# wmk.net
KiCad netlist of a schematic drawn in EAGLE
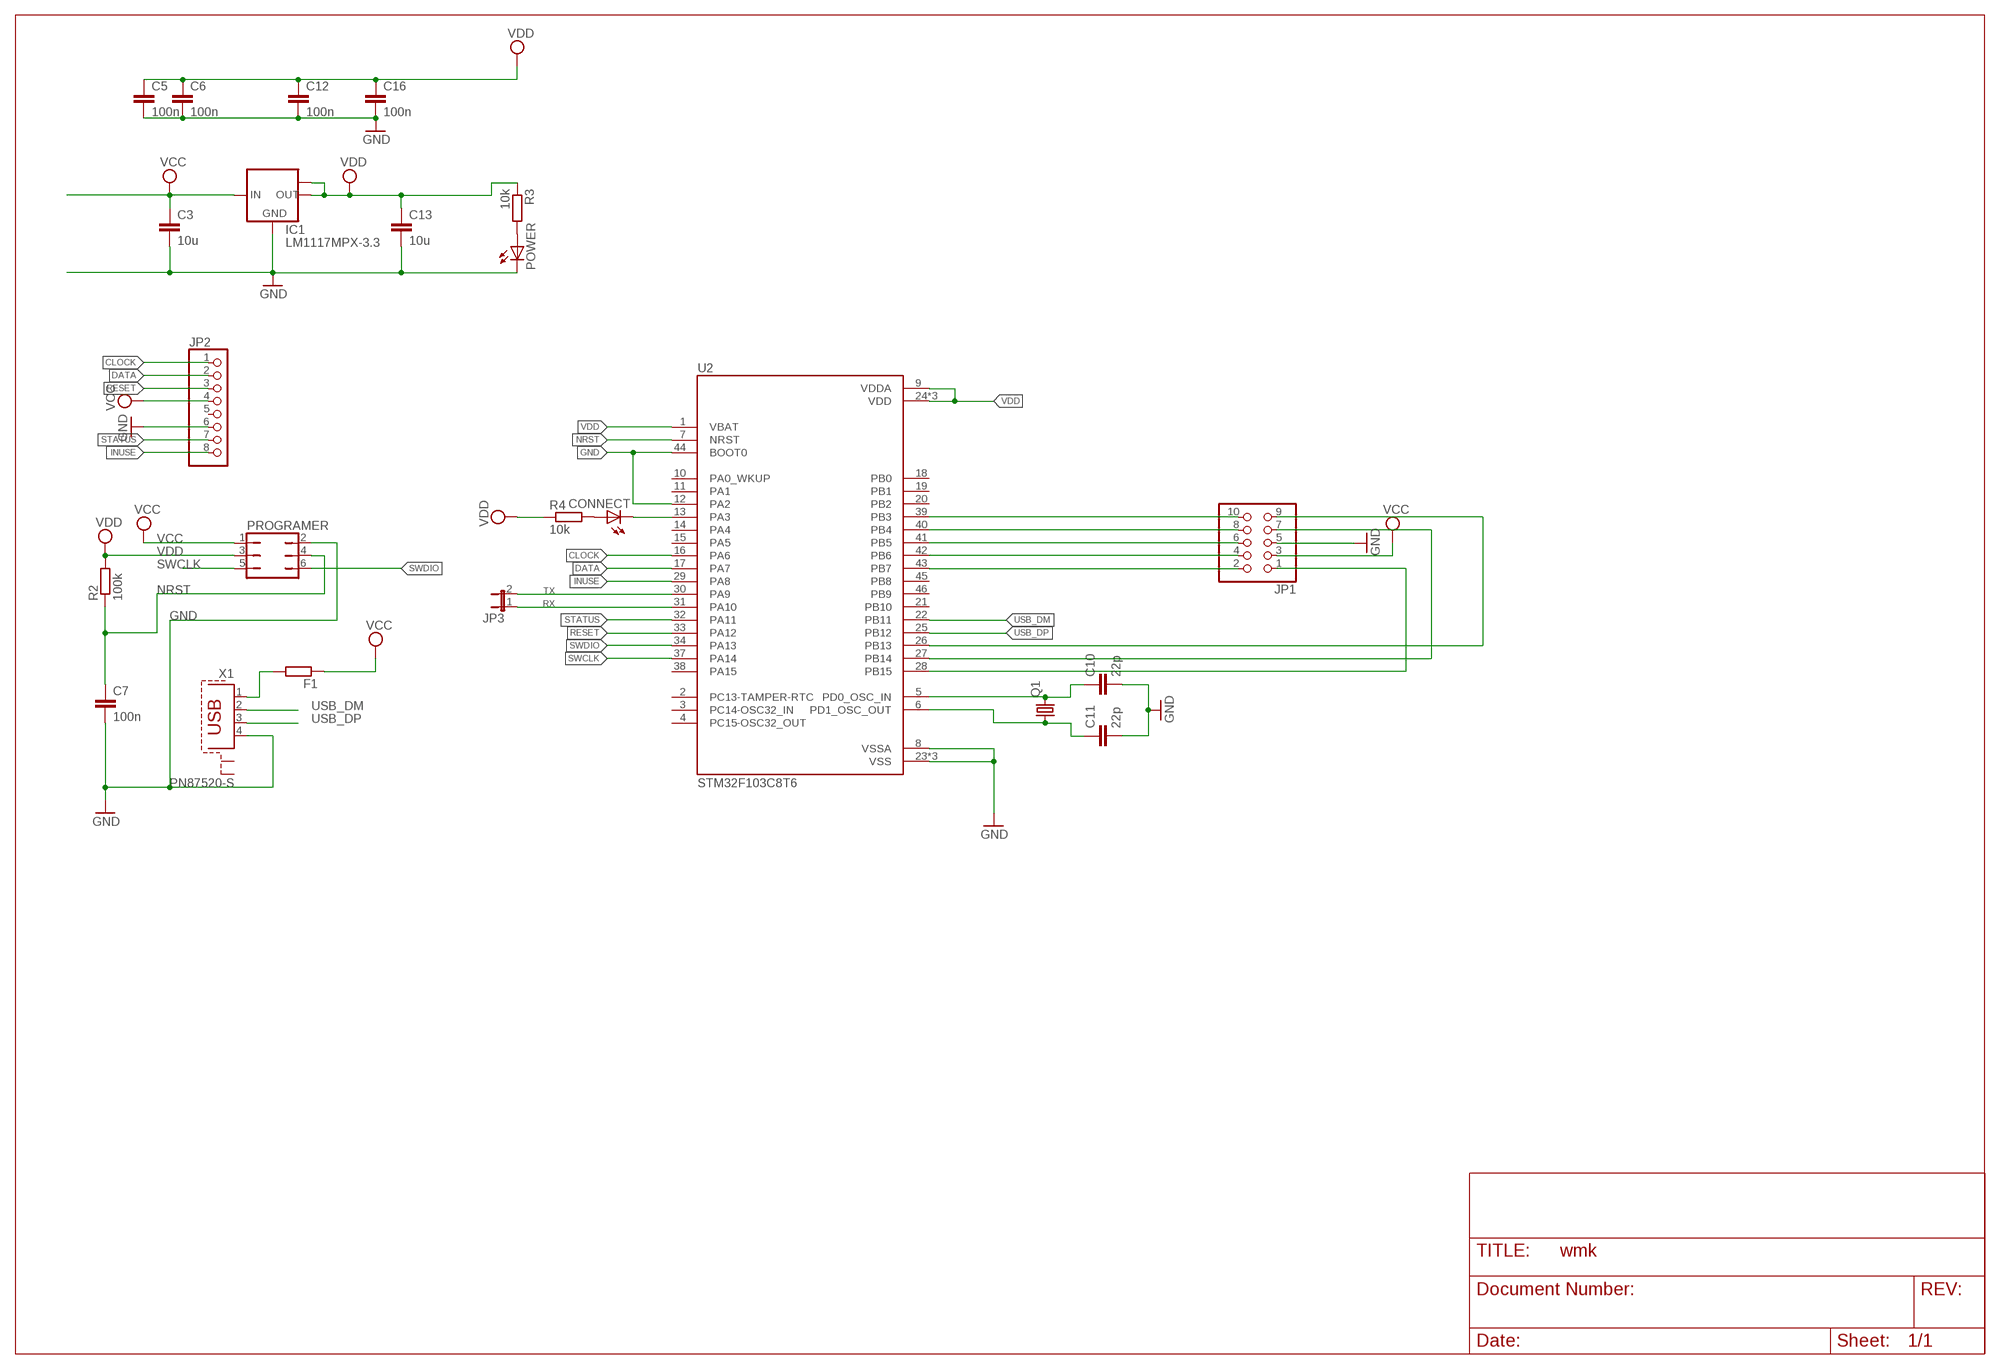
[diagram p0: schematic, sheet 1]

(export (version "E")
  (design (tool "Eeschema 10.0.6"))
  (components
    (comp (ref "C3")
      (value "10u")
      (footprint "eagle-import:C1206")
      (libsource (lib "eagle-import") (part "C-EUC1206"))
    )
    (comp (ref "C5")
      (value "100n")
      (footprint "eagle-import:C0603")
      (libsource (lib "eagle-import") (part "C-EUC0603"))
    )
    (comp (ref "C6")
      (value "100n")
      (footprint "eagle-import:C0603")
      (libsource (lib "eagle-import") (part "C-EUC0603"))
    )
    (comp (ref "C7")
      (value "100n")
      (footprint "eagle-import:C0603")
      (libsource (lib "eagle-import") (part "C-EUC0603"))
    )
    (comp (ref "C10")
      (value "22p")
      (footprint "eagle-import:C0603")
      (libsource (lib "eagle-import") (part "C-EUC0603"))
    )
    (comp (ref "C11")
      (value "22p")
      (footprint "eagle-import:C0603")
      (libsource (lib "eagle-import") (part "C-EUC0603"))
    )
    (comp (ref "C12")
      (value "100n")
      (footprint "eagle-import:C0603")
      (libsource (lib "eagle-import") (part "C-EUC0603"))
    )
    (comp (ref "C13")
      (value "10u")
      (footprint "eagle-import:C1206")
      (libsource (lib "eagle-import") (part "C-EUC1206"))
    )
    (comp (ref "C16")
      (value "100n")
      (footprint "eagle-import:C0603")
      (libsource (lib "eagle-import") (part "C-EUC0603"))
    )
    (comp (ref "CONNECT")
      (value "LEDSML0805")
      (footprint "eagle-import:SML0805")
      (libsource (lib "eagle-import") (part "LEDSML0805"))
    )
    (comp (ref "F1")
      (value "RR1206")
      (footprint "eagle-import:R1206")
      (libsource (lib "eagle-import") (part "RR1206"))
    )
    (comp (ref "IC1")
      (value "LM1117MPX-3.3")
      (footprint "eagle-import:SOT223")
      (libsource (lib "eagle-import") (part "LM1117MPX-3.3"))
    )
    (comp (ref "JP1")
      (value "PINHD-2X5")
      (footprint "eagle-import:2X05")
      (libsource (lib "eagle-import") (part "PINHD-2X5"))
    )
    (comp (ref "JP2")
      (value "PINHD-1X8")
      (footprint "eagle-import:1X08")
      (libsource (lib "eagle-import") (part "PINHD-1X8"))
    )
    (comp (ref "JP3")
      (value "JP1E")
      (footprint "eagle-import:JP1")
      (libsource (lib "eagle-import") (part "JP1E"))
    )
    (comp (ref "POWER")
      (value "LEDSML0805")
      (footprint "eagle-import:SML0805")
      (libsource (lib "eagle-import") (part "LEDSML0805"))
    )
    (comp (ref "PROGRAMER")
      (value "JP3Q")
      (footprint "eagle-import:JP3Q")
      (libsource (lib "eagle-import") (part "JP3Q"))
    )
    (comp (ref "Q1")
      (value "CRYSTALHC49S")
      (footprint "eagle-import:HC49_S")
      (libsource (lib "eagle-import") (part "CRYSTALHC49S"))
    )
    (comp (ref "R2")
      (value "100k")
      (footprint "eagle-import:R0603")
      (libsource (lib "eagle-import") (part "R-EU_R0603"))
    )
    (comp (ref "R3")
      (value "10k")
      (footprint "eagle-import:R0603")
      (libsource (lib "eagle-import") (part "R-EU_R0603"))
    )
    (comp (ref "R4")
      (value "10k")
      (footprint "eagle-import:R0603")
      (libsource (lib "eagle-import") (part "R-EU_R0603"))
    )
    (comp (ref "U2")
      (value "STM32F103C8T6")
      (footprint "eagle-import:QFP50P900X900X160-48N")
      (fields (field (name "MF") "STMicroelectronics"))
      (libsource (lib "eagle-import") (part "STM32F103C8T6"))
    )
    (comp (ref "X1")
      (value "PN87520-S")
      (footprint "eagle-import:PN87520-S")
      (libsource (lib "eagle-import") (part "PN87520-S"))
    )
  )
  (nets
    (net (code "1") (name "/RX") (class "Default")
      (node (ref "JP3") (pin "1") (pinfunction "1_1") (pintype "passive"))
      (node (ref "U2") (pin "31") (pinfunction "PA10_31") (pintype "bidirectional"))
    )
    (net (code "2") (name "/TX") (class "Default")
      (node (ref "JP3") (pin "2") (pinfunction "2_2") (pintype "passive"))
      (node (ref "U2") (pin "30") (pinfunction "PA9_30") (pintype "bidirectional"))
    )
    (net (code "3") (name "CLOCK") (class "Default")
      (node (ref "JP2") (pin "1") (pinfunction "1_1") (pintype "passive"))
      (node (ref "U2") (pin "16") (pinfunction "PA6_16") (pintype "bidirectional"))
    )
    (net (code "4") (name "DATA") (class "Default")
      (node (ref "JP2") (pin "2") (pinfunction "2_2") (pintype "passive"))
      (node (ref "U2") (pin "17") (pinfunction "PA7_17") (pintype "bidirectional"))
    )
    (net (code "5") (name "GND") (class "Default")
      (node (ref "C10") (pin "2") (pinfunction "2_2") (pintype "passive"))
      (node (ref "C11") (pin "2") (pinfunction "2_2") (pintype "passive"))
      (node (ref "C12") (pin "2") (pinfunction "2_2") (pintype "passive"))
      (node (ref "C13") (pin "2") (pinfunction "2_2") (pintype "passive"))
      (node (ref "C16") (pin "2") (pinfunction "2_2") (pintype "passive"))
      (node (ref "C3") (pin "2") (pinfunction "2_2") (pintype "passive"))
      (node (ref "C5") (pin "2") (pinfunction "2_2") (pintype "passive"))
      (node (ref "C6") (pin "2") (pinfunction "2_2") (pintype "passive"))
      (node (ref "C7") (pin "2") (pinfunction "2_2") (pintype "passive"))
      (node (ref "IC1") (pin "1") (pinfunction "GND_1") (pintype "input"))
      (node (ref "JP1") (pin "5") (pinfunction "5_5") (pintype "passive"))
      (node (ref "JP2") (pin "6") (pinfunction "6_6") (pintype "passive"))
      (node (ref "POWER") (pin "C") (pinfunction "C_C") (pintype "passive"))
      (node (ref "PROGRAMER") (pin "2") (pinfunction "2_2") (pintype "passive"))
      (node (ref "U2") (pin "12") (pinfunction "PA2_12") (pintype "bidirectional"))
      (node (ref "U2") (pin "23") (pinfunction "VSS_23") (pintype "power_in"))
      (node (ref "U2") (pin "35") (pinfunction "VSS_35") (pintype "power_in"))
      (node (ref "U2") (pin "44") (pinfunction "BOOT0_44") (pintype "input"))
      (node (ref "U2") (pin "47") (pinfunction "VSS_47") (pintype "power_in"))
      (node (ref "U2") (pin "8") (pinfunction "VSSA_8") (pintype "power_in"))
      (node (ref "X1") (pin "4") (pinfunction "4_4") (pintype "passive"))
    )
    (net (code "6") (name "INUSE") (class "Default")
      (node (ref "JP2") (pin "8") (pinfunction "8_8") (pintype "passive"))
      (node (ref "U2") (pin "29") (pinfunction "PA8_29") (pintype "bidirectional"))
    )
    (net (code "7") (name "NRST") (class "Default")
      (node (ref "C7") (pin "1") (pinfunction "1_1") (pintype "passive"))
      (node (ref "PROGRAMER") (pin "4") (pinfunction "4_4") (pintype "passive"))
      (node (ref "R2") (pin "1") (pinfunction "1_1") (pintype "passive"))
      (node (ref "U2") (pin "7") (pinfunction "NRST_7") (pintype "input"))
    )
    (net (code "8") (name "Net-(CONNECT-PadA)") (class "Default")
      (node (ref "CONNECT") (pin "A") (pinfunction "A_A") (pintype "passive"))
      (node (ref "R4") (pin "2") (pinfunction "2_2") (pintype "passive"))
    )
    (net (code "9") (name "Net-(F1-Pad2)") (class "Default")
      (node (ref "F1") (pin "2") (pinfunction "2_2") (pintype "passive"))
      (node (ref "X1") (pin "1") (pinfunction "1_1") (pintype "passive"))
    )
    (net (code "10") (name "Net-(POWER-PadA)") (class "Default")
      (node (ref "POWER") (pin "A") (pinfunction "A_A") (pintype "passive"))
      (node (ref "R3") (pin "2") (pinfunction "2_2") (pintype "passive"))
    )
    (net (code "11") (name "Net-(U2-PA3)") (class "Default")
      (node (ref "CONNECT") (pin "C") (pinfunction "C_C") (pintype "passive"))
      (node (ref "U2") (pin "13") (pinfunction "PA3_13") (pintype "bidirectional"))
    )
    (net (code "12") (name "Net-(U2-PB3)") (class "Default")
      (node (ref "JP1") (pin "10") (pinfunction "10_10") (pintype "passive"))
      (node (ref "U2") (pin "39") (pinfunction "PB3_39") (pintype "bidirectional"))
    )
    (net (code "13") (name "Net-(U2-PB4)") (class "Default")
      (node (ref "JP1") (pin "8") (pinfunction "8_8") (pintype "passive"))
      (node (ref "U2") (pin "40") (pinfunction "PB4_40") (pintype "bidirectional"))
    )
    (net (code "14") (name "Net-(U2-PB5)") (class "Default")
      (node (ref "JP1") (pin "6") (pinfunction "6_6") (pintype "passive"))
      (node (ref "U2") (pin "41") (pinfunction "PB5_41") (pintype "bidirectional"))
    )
    (net (code "15") (name "Net-(U2-PB6)") (class "Default")
      (node (ref "JP1") (pin "4") (pinfunction "4_4") (pintype "passive"))
      (node (ref "U2") (pin "42") (pinfunction "PB6_42") (pintype "bidirectional"))
    )
    (net (code "16") (name "Net-(U2-PB7)") (class "Default")
      (node (ref "JP1") (pin "2") (pinfunction "2_2") (pintype "passive"))
      (node (ref "U2") (pin "43") (pinfunction "PB7_43") (pintype "bidirectional"))
    )
    (net (code "17") (name "Net-(U2-PB13)") (class "Default")
      (node (ref "JP1") (pin "9") (pinfunction "9_9") (pintype "passive"))
      (node (ref "U2") (pin "26") (pinfunction "PB13_26") (pintype "bidirectional"))
    )
    (net (code "18") (name "Net-(U2-PB14)") (class "Default")
      (node (ref "JP1") (pin "7") (pinfunction "7_7") (pintype "passive"))
      (node (ref "U2") (pin "27") (pinfunction "PB14_27") (pintype "bidirectional"))
    )
    (net (code "19") (name "Net-(U2-PB15)") (class "Default")
      (node (ref "JP1") (pin "1") (pinfunction "1_1") (pintype "passive"))
      (node (ref "U2") (pin "28") (pinfunction "PB15_28") (pintype "bidirectional"))
    )
    (net (code "20") (name "Net-(U2-PD0_OSC_IN)") (class "Default")
      (node (ref "C10") (pin "1") (pinfunction "1_1") (pintype "passive"))
      (node (ref "Q1") (pin "2") (pinfunction "2_2") (pintype "passive"))
      (node (ref "U2") (pin "5") (pinfunction "PD0_OSC_IN_5") (pintype "bidirectional"))
    )
    (net (code "21") (name "Net-(U2-PD1_OSC_OUT)") (class "Default")
      (node (ref "C11") (pin "1") (pinfunction "1_1") (pintype "passive"))
      (node (ref "Q1") (pin "1") (pinfunction "1_1") (pintype "passive"))
      (node (ref "U2") (pin "6") (pinfunction "PD1_OSC_OUT_6") (pintype "bidirectional"))
    )
    (net (code "22") (name "RESET") (class "Default")
      (node (ref "JP2") (pin "3") (pinfunction "3_3") (pintype "passive"))
      (node (ref "U2") (pin "33") (pinfunction "PA12_33") (pintype "bidirectional"))
    )
    (net (code "23") (name "STATUS") (class "Default")
      (node (ref "JP2") (pin "7") (pinfunction "7_7") (pintype "passive"))
      (node (ref "U2") (pin "32") (pinfunction "PA11_32") (pintype "bidirectional"))
    )
    (net (code "24") (name "SWCLK") (class "Default")
      (node (ref "PROGRAMER") (pin "5") (pinfunction "5_5") (pintype "passive"))
      (node (ref "U2") (pin "37") (pinfunction "PA14_37") (pintype "bidirectional"))
    )
    (net (code "25") (name "SWDIO") (class "Default")
      (node (ref "PROGRAMER") (pin "6") (pinfunction "6_6") (pintype "passive"))
      (node (ref "U2") (pin "34") (pinfunction "PA13_34") (pintype "bidirectional"))
    )
    (net (code "26") (name "USB_DM") (class "Default")
      (node (ref "U2") (pin "22") (pinfunction "PB11_22") (pintype "bidirectional"))
      (node (ref "X1") (pin "2") (pinfunction "2_2") (pintype "passive"))
    )
    (net (code "27") (name "USB_DP") (class "Default")
      (node (ref "U2") (pin "25") (pinfunction "PB12_25") (pintype "bidirectional"))
      (node (ref "X1") (pin "3") (pinfunction "3_3") (pintype "passive"))
    )
    (net (code "28") (name "VCC") (class "Default")
      (node (ref "C3") (pin "1") (pinfunction "1_1") (pintype "passive"))
      (node (ref "F1") (pin "1") (pinfunction "1_1") (pintype "passive"))
      (node (ref "IC1") (pin "3") (pinfunction "IN_3") (pintype "input"))
      (node (ref "JP1") (pin "3") (pinfunction "3_3") (pintype "passive"))
      (node (ref "JP2") (pin "4") (pinfunction "4_4") (pintype "passive"))
      (node (ref "PROGRAMER") (pin "1") (pinfunction "1_1") (pintype "passive"))
    )
    (net (code "29") (name "VDD") (class "Default")
      (node (ref "C12") (pin "1") (pinfunction "1_1") (pintype "passive"))
      (node (ref "C13") (pin "1") (pinfunction "1_1") (pintype "passive"))
      (node (ref "C16") (pin "1") (pinfunction "1_1") (pintype "passive"))
      (node (ref "C5") (pin "1") (pinfunction "1_1") (pintype "passive"))
      (node (ref "C6") (pin "1") (pinfunction "1_1") (pintype "passive"))
      (node (ref "IC1") (pin "2") (pinfunction "OUT_2") (pintype "passive"))
      (node (ref "IC1") (pin "TAB") (pinfunction "OUT1_TAB") (pintype "passive"))
      (node (ref "PROGRAMER") (pin "3") (pinfunction "3_3") (pintype "passive"))
      (node (ref "R2") (pin "2") (pinfunction "2_2") (pintype "passive"))
      (node (ref "R3") (pin "1") (pinfunction "1_1") (pintype "passive"))
      (node (ref "R4") (pin "1") (pinfunction "1_1") (pintype "passive"))
      (node (ref "U2") (pin "1") (pinfunction "VBAT_1") (pintype "bidirectional"))
      (node (ref "U2") (pin "24") (pinfunction "VDD_24") (pintype "power_in"))
      (node (ref "U2") (pin "36") (pinfunction "VDD_36") (pintype "power_in"))
      (node (ref "U2") (pin "48") (pinfunction "VDD_48") (pintype "power_in"))
      (node (ref "U2") (pin "9") (pinfunction "VDDA_9") (pintype "power_in"))
    )
    (net (code "30") (name "unconnected-(JP2-Pad5)") (class "Default")
      (node (ref "JP2") (pin "5") (pinfunction "5_5") (pintype "passive"))
    )
    (net (code "31") (name "unconnected-(U2-PA0_WKUP-Pad10)") (class "Default")
      (node (ref "U2") (pin "10") (pinfunction "PA0_WKUP_10") (pintype "bidirectional"))
    )
    (net (code "32") (name "unconnected-(U2-PA1-Pad11)") (class "Default")
      (node (ref "U2") (pin "11") (pinfunction "PA1_11") (pintype "bidirectional"))
    )
    (net (code "33") (name "unconnected-(U2-PA4-Pad14)") (class "Default")
      (node (ref "U2") (pin "14") (pinfunction "PA4_14") (pintype "bidirectional"))
    )
    (net (code "34") (name "unconnected-(U2-PA5-Pad15)") (class "Default")
      (node (ref "U2") (pin "15") (pinfunction "PA5_15") (pintype "bidirectional"))
    )
    (net (code "35") (name "unconnected-(U2-PA15-Pad38)") (class "Default")
      (node (ref "U2") (pin "38") (pinfunction "PA15_38") (pintype "bidirectional"))
    )
    (net (code "36") (name "unconnected-(U2-PB0-Pad18)") (class "Default")
      (node (ref "U2") (pin "18") (pinfunction "PB0_18") (pintype "bidirectional"))
    )
    (net (code "37") (name "unconnected-(U2-PB1-Pad19)") (class "Default")
      (node (ref "U2") (pin "19") (pinfunction "PB1_19") (pintype "bidirectional"))
    )
    (net (code "38") (name "unconnected-(U2-PB2-Pad20)") (class "Default")
      (node (ref "U2") (pin "20") (pinfunction "PB2_20") (pintype "bidirectional"))
    )
    (net (code "39") (name "unconnected-(U2-PB8-Pad45)") (class "Default")
      (node (ref "U2") (pin "45") (pinfunction "PB8_45") (pintype "bidirectional"))
    )
    (net (code "40") (name "unconnected-(U2-PB9-Pad46)") (class "Default")
      (node (ref "U2") (pin "46") (pinfunction "PB9_46") (pintype "bidirectional"))
    )
    (net (code "41") (name "unconnected-(U2-PB10-Pad21)") (class "Default")
      (node (ref "U2") (pin "21") (pinfunction "PB10_21") (pintype "bidirectional"))
    )
    (net (code "42") (name "unconnected-(U2-PC13-TAMPER-RTC-Pad2)") (class "Default")
      (node (ref "U2") (pin "2") (pinfunction "PC13-TAMPER-RTC_2") (pintype "bidirectional"))
    )
    (net (code "43") (name "unconnected-(U2-PC14-OSC32_IN-Pad3)") (class "Default")
      (node (ref "U2") (pin "3") (pinfunction "PC14-OSC32_IN_3") (pintype "bidirectional"))
    )
    (net (code "44") (name "unconnected-(U2-PC15-OSC32_OUT-Pad4)") (class "Default")
      (node (ref "U2") (pin "4") (pinfunction "PC15-OSC32_OUT_4") (pintype "bidirectional"))
    )
    (net (code "45") (name "unconnected-(X1-PadS1)") (class "Default")
      (node (ref "X1") (pin "S1") (pinfunction "S1_S1") (pintype "passive"))
    )
    (net (code "46") (name "unconnected-(X1-PadS2)") (class "Default")
      (node (ref "X1") (pin "S2") (pinfunction "S2_S2") (pintype "passive"))
    )
  )
)
